# PIO.net
KiCad netlist of a schematic drawn in Altium Designer
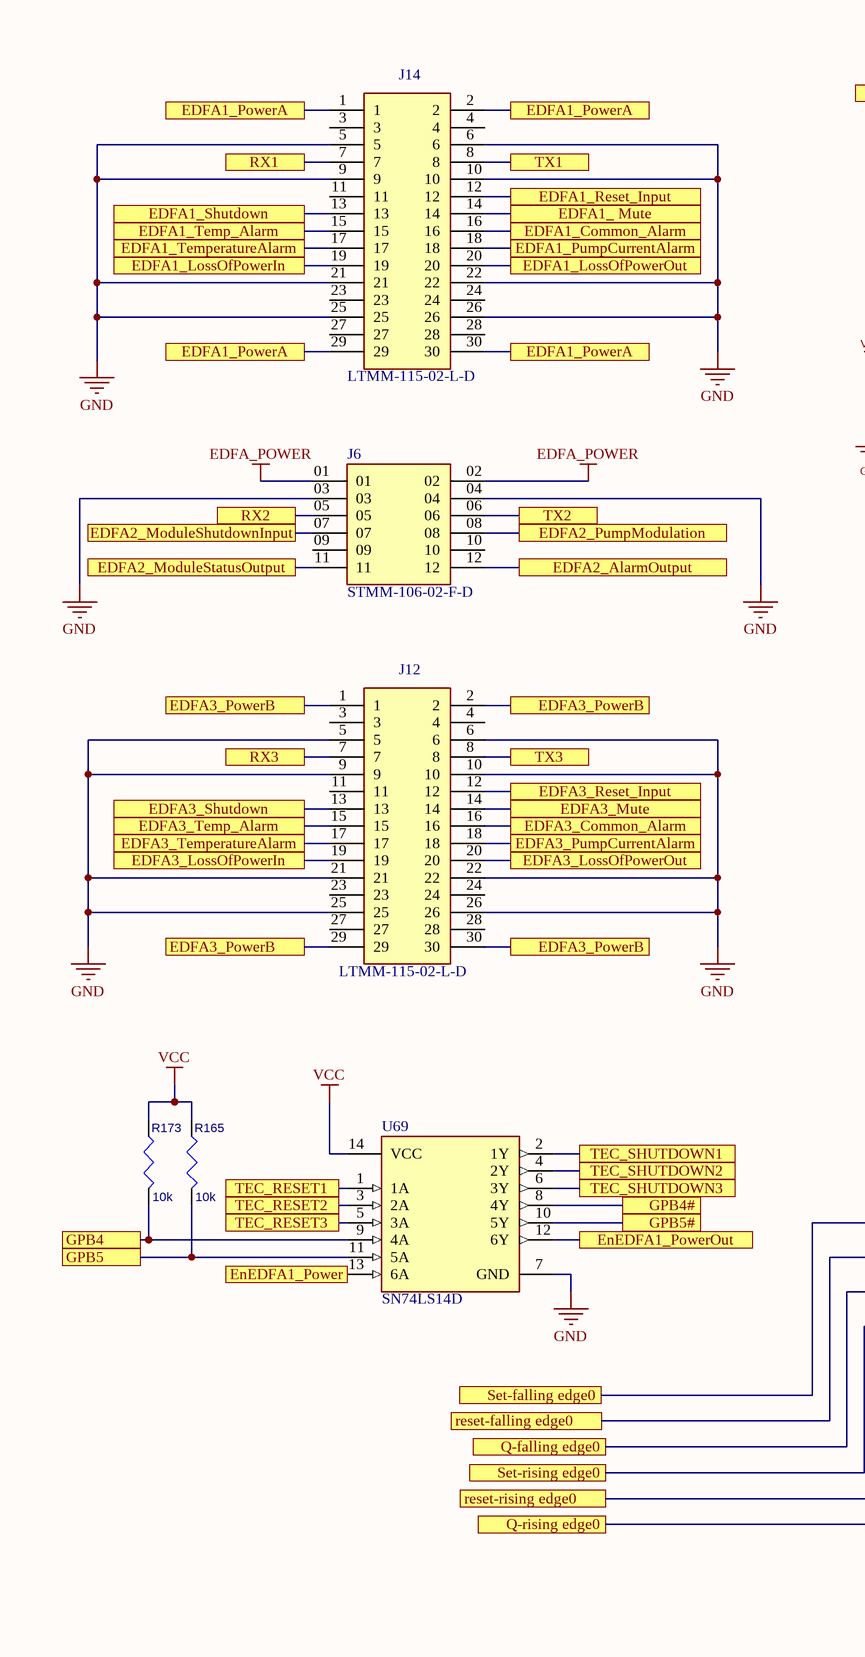
[diagram p0: PIO.SchDoc, left]
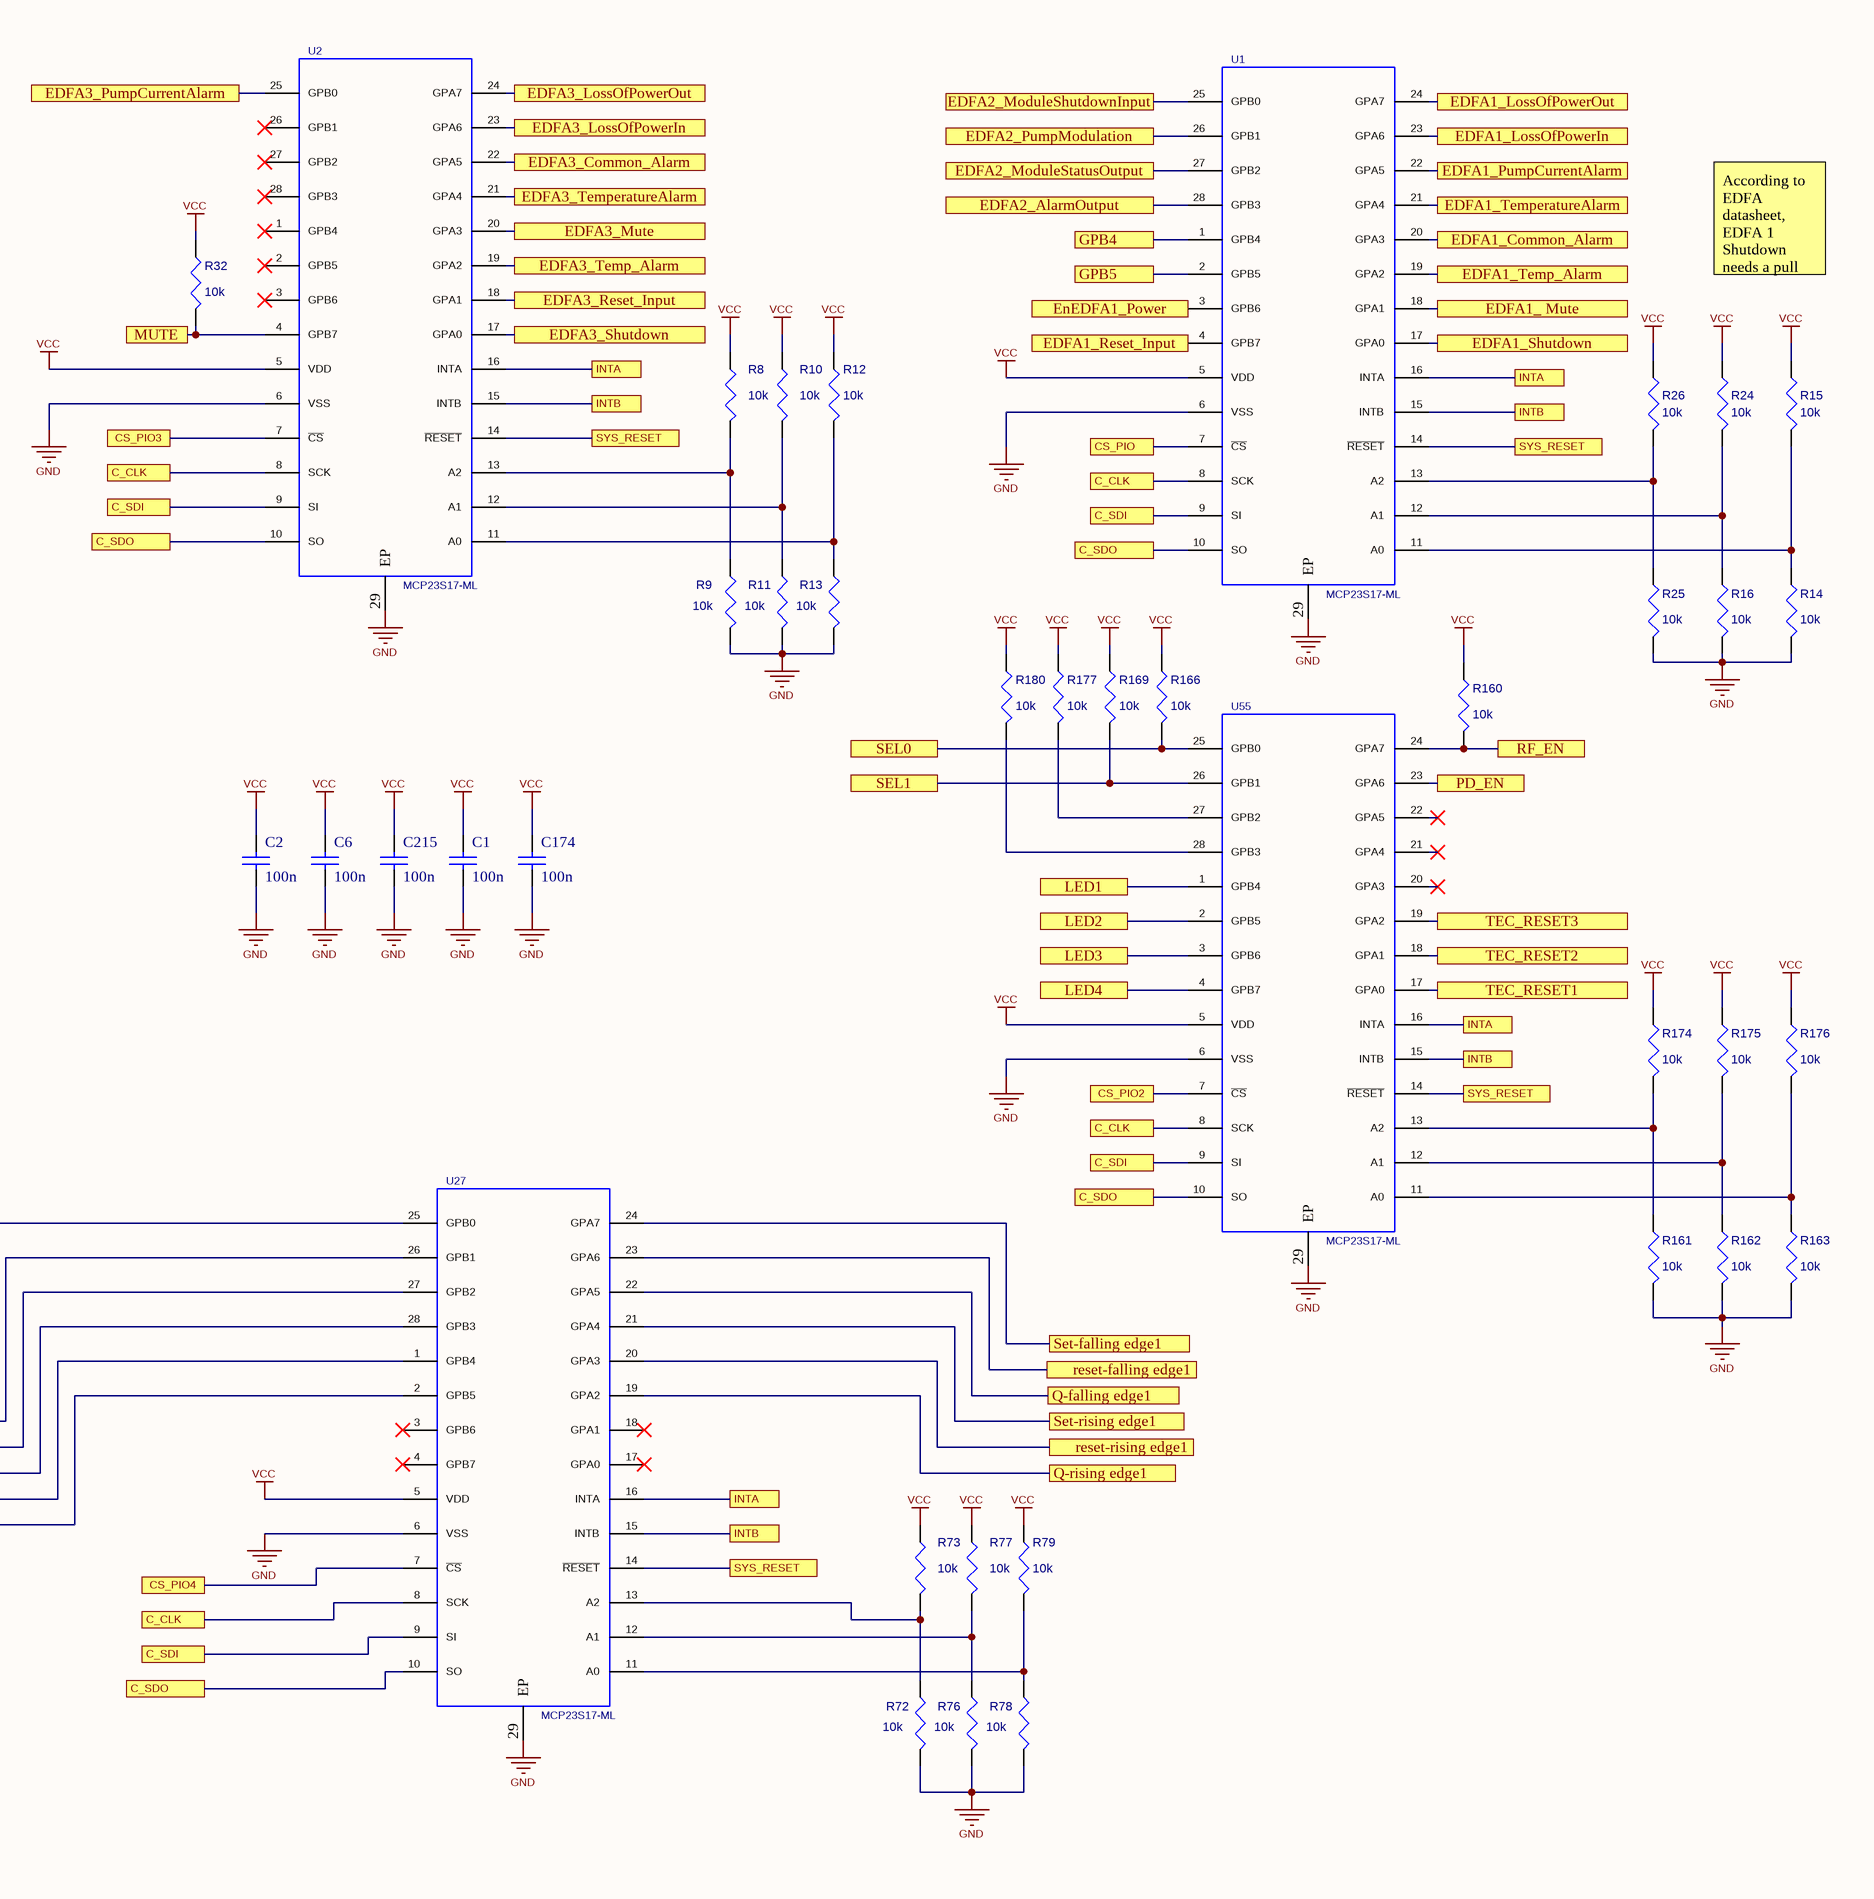
[diagram p1: PIO.SchDoc, right]

(export (version "E")
  (design (tool "Eeschema 10.0.6"))
  (components
    (comp (ref "C1")
      (value "100n")
      (footprint "CAPC1608X90X35LL15T15")
      (description "Chip Capacitor, 100 nF, +/- 10%, 50 V, -55 to 125 degC, 0603 (1608 Metric), RoHS, Tape and Reel")
      (fields (field (name "TOLERANCE") "10%") (field (name "MANUFACTURER") "KEMET"))
      (libsource (lib "xDAC_Carrier") (part "CMP-1035-02592-3"))
    )
    (comp (ref "C2")
      (value "100n")
      (footprint "CAPC1608X90X35LL15T15")
      (description "Chip Capacitor, 100 nF, +/- 10%, 50 V, -55 to 125 degC, 0603 (1608 Metric), RoHS, Tape and Reel")
      (fields (field (name "TOLERANCE") "10%") (field (name "MANUFACTURER") "KEMET"))
      (libsource (lib "xDAC_Carrier") (part "CMP-1035-02592-3"))
    )
    (comp (ref "C6")
      (value "100n")
      (footprint "CAPC1608X90X35LL15T15")
      (description "Chip Capacitor, 100 nF, +/- 10%, 50 V, -55 to 125 degC, 0603 (1608 Metric), RoHS, Tape and Reel")
      (fields (field (name "TOLERANCE") "10%") (field (name "MANUFACTURER") "KEMET"))
      (libsource (lib "xDAC_Carrier") (part "CMP-1035-02592-3"))
    )
    (comp (ref "C174")
      (value "100n")
      (footprint "CAPC1608X90X35LL15T15")
      (description "Chip Capacitor, 100 nF, +/- 10%, 50 V, -55 to 125 degC, 0603 (1608 Metric), RoHS, Tape and Reel")
      (fields (field (name "TOLERANCE") "10%") (field (name "MANUFACTURER") "KEMET"))
      (libsource (lib "xDAC_Carrier") (part "CMP-1035-02592-3"))
    )
    (comp (ref "C215")
      (value "100n")
      (footprint "CAPC1608X90X35LL15T15")
      (description "Chip Capacitor, 100 nF, +/- 10%, 50 V, -55 to 125 degC, 0603 (1608 Metric), RoHS, Tape and Reel")
      (fields (field (name "TOLERANCE") "10%") (field (name "MANUFACTURER") "KEMET"))
      (libsource (lib "xDAC_Carrier") (part "CMP-1035-02592-3"))
    )
    (comp (ref "J6")
      (value "STMM-106-02-F-D")
      (footprint "SAMTEC_STMM-106-02-F-D")
      (description "Connector Header Surface Mount 12 position 0.079 (2.00mm)")
      (fields (field (name "MF") "Samtec"))
      (libsource (lib "xDAC_Carrier") (part "STMM-106-02-F-D"))
    )
    (comp (ref "J12")
      (value "LTMM-115-02-L-D")
      (footprint "SHDR30W51P200_2X15_3239X651X480P")
      (description "Connector")
      (fields (field (name "MOUSER PART NUMBER") "200-LTMM11502LD"))
      (libsource (lib "xDAC_Carrier") (part "LTMM-115-02-L-D"))
    )
    (comp (ref "J14")
      (value "LTMM-115-02-L-D")
      (footprint "SHDR30W51P200_2X15_3239X651X480P")
      (description "Connector")
      (fields (field (name "MOUSER PART NUMBER") "200-LTMM11502LD"))
      (libsource (lib "xDAC_Carrier") (part "LTMM-115-02-L-D"))
    )
    (comp (ref "R8")
      (value "10k")
      (footprint "CR0603N")
      (description "RES.,10k OHMS,1%,1/10W,0603")
      (fields (field (name "MANUFACTURER") "PANASONIC") (field (name "TOLERANCE") "1%"))
      (libsource (lib "xDAC_Carrier") (part "RES"))
    )
    (comp (ref "R9")
      (value "10k")
      (footprint "CR0603N")
      (description "RES.,10k OHMS,1%,1/10W,0603")
      (fields (field (name "MANUFACTURER") "PANASONIC") (field (name "TOLERANCE") "1%"))
      (libsource (lib "xDAC_Carrier") (part "RES"))
    )
    (comp (ref "R10")
      (value "10k")
      (footprint "CR0603N")
      (description "RES.,10k OHMS,1%,1/10W,0603")
      (fields (field (name "MANUFACTURER") "PANASONIC") (field (name "TOLERANCE") "1%"))
      (libsource (lib "xDAC_Carrier") (part "RES"))
    )
    (comp (ref "R11")
      (value "10k")
      (footprint "CR0603N")
      (description "RES.,10k OHMS,1%,1/10W,0603")
      (fields (field (name "MANUFACTURER") "PANASONIC") (field (name "TOLERANCE") "1%"))
      (libsource (lib "xDAC_Carrier") (part "RES"))
    )
    (comp (ref "R12")
      (value "10k")
      (footprint "CR0603N")
      (description "RES.,10k OHMS,1%,1/10W,0603")
      (fields (field (name "MANUFACTURER") "PANASONIC") (field (name "TOLERANCE") "1%"))
      (libsource (lib "xDAC_Carrier") (part "RES"))
    )
    (comp (ref "R13")
      (value "10k")
      (footprint "CR0603N")
      (description "RES.,10k OHMS,1%,1/10W,0603")
      (fields (field (name "MANUFACTURER") "PANASONIC") (field (name "TOLERANCE") "1%"))
      (libsource (lib "xDAC_Carrier") (part "RES"))
    )
    (comp (ref "R14")
      (value "10k")
      (footprint "CR0603N")
      (description "RES.,10k OHMS,1%,1/10W,0603")
      (fields (field (name "MANUFACTURER") "PANASONIC") (field (name "TOLERANCE") "1%"))
      (libsource (lib "xDAC_Carrier") (part "RES"))
    )
    (comp (ref "R15")
      (value "10k")
      (footprint "CR0603N")
      (description "RES.,10k OHMS,1%,1/10W,0603")
      (fields (field (name "MANUFACTURER") "PANASONIC") (field (name "TOLERANCE") "1%"))
      (libsource (lib "xDAC_Carrier") (part "RES"))
    )
    (comp (ref "R16")
      (value "10k")
      (footprint "CR0603N")
      (description "RES.,10k OHMS,1%,1/10W,0603")
      (fields (field (name "MANUFACTURER") "PANASONIC") (field (name "TOLERANCE") "1%"))
      (libsource (lib "xDAC_Carrier") (part "RES"))
    )
    (comp (ref "R24")
      (value "10k")
      (footprint "CR0603N")
      (description "RES.,10k OHMS,1%,1/10W,0603")
      (fields (field (name "MANUFACTURER") "PANASONIC") (field (name "TOLERANCE") "1%"))
      (libsource (lib "xDAC_Carrier") (part "RES"))
    )
    (comp (ref "R25")
      (value "10k")
      (footprint "CR0603N")
      (description "RES.,10k OHMS,1%,1/10W,0603")
      (fields (field (name "MANUFACTURER") "PANASONIC") (field (name "TOLERANCE") "1%"))
      (libsource (lib "xDAC_Carrier") (part "RES"))
    )
    (comp (ref "R26")
      (value "10k")
      (footprint "CR0603N")
      (description "RES.,10k OHMS,1%,1/10W,0603")
      (fields (field (name "MANUFACTURER") "PANASONIC") (field (name "TOLERANCE") "1%"))
      (libsource (lib "xDAC_Carrier") (part "RES"))
    )
    (comp (ref "R32")
      (value "10k")
      (footprint "CR0603N")
      (description "RES.,10k OHMS,1%,1/10W,0603")
      (fields (field (name "MANUFACTURER") "PANASONIC") (field (name "TOLERANCE") "1%"))
      (libsource (lib "xDAC_Carrier") (part "RES"))
    )
    (comp (ref "R72")
      (value "10k")
      (footprint "CR0603N")
      (description "RES.,10k OHMS,1%,1/10W,0603")
      (fields (field (name "MANUFACTURER") "PANASONIC") (field (name "TOLERANCE") "1%"))
      (libsource (lib "xDAC_Carrier") (part "RES"))
    )
    (comp (ref "R73")
      (value "10k")
      (footprint "CR0603N")
      (description "RES.,10k OHMS,1%,1/10W,0603")
      (fields (field (name "MANUFACTURER") "PANASONIC") (field (name "TOLERANCE") "1%"))
      (libsource (lib "xDAC_Carrier") (part "RES"))
    )
    (comp (ref "R76")
      (value "10k")
      (footprint "CR0603N")
      (description "RES.,10k OHMS,1%,1/10W,0603")
      (fields (field (name "MANUFACTURER") "PANASONIC") (field (name "TOLERANCE") "1%"))
      (libsource (lib "xDAC_Carrier") (part "RES"))
    )
    (comp (ref "R77")
      (value "10k")
      (footprint "CR0603N")
      (description "RES.,10k OHMS,1%,1/10W,0603")
      (fields (field (name "MANUFACTURER") "PANASONIC") (field (name "TOLERANCE") "1%"))
      (libsource (lib "xDAC_Carrier") (part "RES"))
    )
    (comp (ref "R78")
      (value "10k")
      (footprint "CR0603N")
      (description "RES.,10k OHMS,1%,1/10W,0603")
      (fields (field (name "MANUFACTURER") "PANASONIC") (field (name "TOLERANCE") "1%"))
      (libsource (lib "xDAC_Carrier") (part "RES"))
    )
    (comp (ref "R79")
      (value "10k")
      (footprint "CR0603N")
      (description "RES.,10k OHMS,1%,1/10W,0603")
      (fields (field (name "MANUFACTURER") "PANASONIC") (field (name "TOLERANCE") "1%"))
      (libsource (lib "xDAC_Carrier") (part "RES"))
    )
    (comp (ref "R160")
      (value "10k")
      (footprint "CR0603N")
      (description "RES.,10k OHMS,1%,1/10W,0603")
      (fields (field (name "MANUFACTURER") "PANASONIC") (field (name "TOLERANCE") "1%"))
      (libsource (lib "xDAC_Carrier") (part "RES"))
    )
    (comp (ref "R161")
      (value "10k")
      (footprint "CR0603N")
      (description "RES.,10k OHMS,1%,1/10W,0603")
      (fields (field (name "MANUFACTURER") "PANASONIC") (field (name "TOLERANCE") "1%"))
      (libsource (lib "xDAC_Carrier") (part "RES"))
    )
    (comp (ref "R162")
      (value "10k")
      (footprint "CR0603N")
      (description "RES.,10k OHMS,1%,1/10W,0603")
      (fields (field (name "MANUFACTURER") "PANASONIC") (field (name "TOLERANCE") "1%"))
      (libsource (lib "xDAC_Carrier") (part "RES"))
    )
    (comp (ref "R163")
      (value "10k")
      (footprint "CR0603N")
      (description "RES.,10k OHMS,1%,1/10W,0603")
      (fields (field (name "MANUFACTURER") "PANASONIC") (field (name "TOLERANCE") "1%"))
      (libsource (lib "xDAC_Carrier") (part "RES"))
    )
    (comp (ref "R165")
      (value "10k")
      (footprint "CR0603N")
      (description "RES.,10k OHMS,1%,1/10W,0603")
      (fields (field (name "MANUFACTURER") "PANASONIC") (field (name "TOLERANCE") "1%"))
      (libsource (lib "xDAC_Carrier") (part "RES"))
    )
    (comp (ref "R166")
      (value "10k")
      (footprint "CR0603N")
      (description "RES.,10k OHMS,1%,1/10W,0603")
      (fields (field (name "MANUFACTURER") "PANASONIC") (field (name "TOLERANCE") "1%"))
      (libsource (lib "xDAC_Carrier") (part "RES"))
    )
    (comp (ref "R169")
      (value "10k")
      (footprint "CR0603N")
      (description "RES.,10k OHMS,1%,1/10W,0603")
      (fields (field (name "MANUFACTURER") "PANASONIC") (field (name "TOLERANCE") "1%"))
      (libsource (lib "xDAC_Carrier") (part "RES"))
    )
    (comp (ref "R173")
      (value "10k")
      (footprint "CR0603N")
      (description "RES.,10k OHMS,1%,1/10W,0603")
      (fields (field (name "MANUFACTURER") "PANASONIC") (field (name "TOLERANCE") "1%"))
      (libsource (lib "xDAC_Carrier") (part "RES"))
    )
    (comp (ref "R174")
      (value "10k")
      (footprint "CR0603N")
      (description "RES.,10k OHMS,1%,1/10W,0603")
      (fields (field (name "MANUFACTURER") "PANASONIC") (field (name "TOLERANCE") "1%"))
      (libsource (lib "xDAC_Carrier") (part "RES"))
    )
    (comp (ref "R175")
      (value "10k")
      (footprint "CR0603N")
      (description "RES.,10k OHMS,1%,1/10W,0603")
      (fields (field (name "MANUFACTURER") "PANASONIC") (field (name "TOLERANCE") "1%"))
      (libsource (lib "xDAC_Carrier") (part "RES"))
    )
    (comp (ref "R176")
      (value "10k")
      (footprint "CR0603N")
      (description "RES.,10k OHMS,1%,1/10W,0603")
      (fields (field (name "MANUFACTURER") "PANASONIC") (field (name "TOLERANCE") "1%"))
      (libsource (lib "xDAC_Carrier") (part "RES"))
    )
    (comp (ref "R177")
      (value "10k")
      (footprint "CR0603N")
      (description "RES.,10k OHMS,1%,1/10W,0603")
      (fields (field (name "MANUFACTURER") "PANASONIC") (field (name "TOLERANCE") "1%"))
      (libsource (lib "xDAC_Carrier") (part "RES"))
    )
    (comp (ref "R180")
      (value "10k")
      (footprint "CR0603N")
      (description "RES.,10k OHMS,1%,1/10W,0603")
      (fields (field (name "MANUFACTURER") "PANASONIC") (field (name "TOLERANCE") "1%"))
      (libsource (lib "xDAC_Carrier") (part "RES"))
    )
    (comp (ref "U1")
      (value "MCP23S17-ML")
      (footprint "QFN65P600X600X100-29VN")
      (fields (field (name "MANUFACTURER") "Microchip") (field (name "PART NO") "MCP23S17-E/ML"))
      (libsource (lib "xDAC_Carrier") (part "MCP23S17-ML"))
    )
    (comp (ref "U2")
      (value "MCP23S17-ML")
      (footprint "QFN65P600X600X100-29VN")
      (fields (field (name "MANUFACTURER") "Microchip") (field (name "PART NO") "MCP23S17-E/ML"))
      (libsource (lib "xDAC_Carrier") (part "MCP23S17-ML"))
    )
    (comp (ref "U27")
      (value "MCP23S17-ML")
      (footprint "QFN65P600X600X100-29VN")
      (fields (field (name "MANUFACTURER") "Microchip") (field (name "PART NO") "MCP23S17-E/ML"))
      (libsource (lib "xDAC_Carrier") (part "MCP23S17-ML"))
    )
    (comp (ref "U55")
      (value "MCP23S17-ML")
      (footprint "QFN65P600X600X100-29VN")
      (fields (field (name "MANUFACTURER") "Microchip") (field (name "PART NO") "MCP23S17-E/ML"))
      (libsource (lib "xDAC_Carrier") (part "MCP23S17-ML"))
    )
    (comp (ref "U69")
      (value "SN74LS14D")
      (footprint "FP-D0014A-MFG")
      (description "IC INVERTER SCHMITT 6CH 14SOIC")
      (fields
        (field (name "OCTOPART") "https://octopart.com/sn74ls14d-texas+instruments-464458")
        (field (name "MANUFACTURER") "Texas Instruments")
      )
      (libsource (lib "Altium Content Vault") (part "988d500a1b54a36af656cee24e4e601"))
    )
  )
  (nets
    (net (code "1") (name "/CS_PIO") (class "Default")
      (node (ref "U1") (pin "7") (pinfunction "CS_7") (pintype "passive"))
    )
    (net (code "2") (name "/CS_PIO2") (class "Default")
      (node (ref "U55") (pin "7") (pinfunction "CS_7") (pintype "passive"))
    )
    (net (code "3") (name "/CS_PIO3") (class "Default")
      (node (ref "U2") (pin "7") (pinfunction "CS_7") (pintype "passive"))
    )
    (net (code "4") (name "/CS_PIO4") (class "Default")
      (node (ref "U27") (pin "7") (pinfunction "CS_7") (pintype "passive"))
    )
    (net (code "5") (name "/C_CLK") (class "Default")
      (node (ref "U1") (pin "8") (pinfunction "SCK_8") (pintype "passive"))
      (node (ref "U2") (pin "8") (pinfunction "SCK_8") (pintype "passive"))
      (node (ref "U27") (pin "8") (pinfunction "SCK_8") (pintype "passive"))
      (node (ref "U55") (pin "8") (pinfunction "SCK_8") (pintype "passive"))
    )
    (net (code "6") (name "/C_SDI") (class "Default")
      (node (ref "U1") (pin "9") (pinfunction "SI_9") (pintype "passive"))
      (node (ref "U2") (pin "9") (pinfunction "SI_9") (pintype "passive"))
      (node (ref "U27") (pin "9") (pinfunction "SI_9") (pintype "passive"))
      (node (ref "U55") (pin "9") (pinfunction "SI_9") (pintype "passive"))
    )
    (net (code "7") (name "/C_SDO") (class "Default")
      (node (ref "U1") (pin "10") (pinfunction "SO_10") (pintype "passive"))
      (node (ref "U2") (pin "10") (pinfunction "SO_10") (pintype "passive"))
      (node (ref "U27") (pin "10") (pinfunction "SO_10") (pintype "passive"))
      (node (ref "U55") (pin "10") (pinfunction "SO_10") (pintype "passive"))
    )
    (net (code "8") (name "/EDFA1_ Mute") (class "Default")
      (node (ref "J14") (pin "14") (pinfunction "14_14") (pintype "passive"))
      (node (ref "U1") (pin "18") (pinfunction "GPA1_18") (pintype "passive"))
    )
    (net (code "9") (name "/EDFA1_Common_Alarm") (class "Default")
      (node (ref "J14") (pin "16") (pinfunction "16_16") (pintype "passive"))
      (node (ref "U1") (pin "20") (pinfunction "GPA3_20") (pintype "passive"))
    )
    (net (code "10") (name "/EDFA1_LossOfPowerIn") (class "Default")
      (node (ref "J14") (pin "19") (pinfunction "19_19") (pintype "passive"))
      (node (ref "U1") (pin "23") (pinfunction "GPA6_23") (pintype "passive"))
    )
    (net (code "11") (name "/EDFA1_LossOfPowerOut") (class "Default")
      (node (ref "J14") (pin "20") (pinfunction "20_20") (pintype "passive"))
      (node (ref "U1") (pin "24") (pinfunction "GPA7_24") (pintype "passive"))
    )
    (net (code "12") (name "/EDFA1_PowerA") (class "Default")
      (node (ref "J14") (pin "1") (pinfunction "1_1") (pintype "passive"))
      (node (ref "J14") (pin "2") (pinfunction "2_2") (pintype "passive"))
      (node (ref "J14") (pin "29") (pinfunction "29_29") (pintype "passive"))
      (node (ref "J14") (pin "30") (pinfunction "30_30") (pintype "passive"))
    )
    (net (code "13") (name "/EDFA1_PumpCurrentAlarm") (class "Default")
      (node (ref "J14") (pin "18") (pinfunction "18_18") (pintype "passive"))
      (node (ref "U1") (pin "22") (pinfunction "GPA5_22") (pintype "passive"))
    )
    (net (code "14") (name "/EDFA1_Reset_Input") (class "Default")
      (node (ref "J14") (pin "12") (pinfunction "12_12") (pintype "passive"))
      (node (ref "U1") (pin "4") (pinfunction "GPB7_4") (pintype "passive"))
    )
    (net (code "15") (name "/EDFA1_Shutdown") (class "Default")
      (node (ref "J14") (pin "13") (pinfunction "13_13") (pintype "passive"))
      (node (ref "U1") (pin "17") (pinfunction "GPA0_17") (pintype "passive"))
    )
    (net (code "16") (name "/EDFA1_Temp_Alarm") (class "Default")
      (node (ref "J14") (pin "15") (pinfunction "15_15") (pintype "passive"))
      (node (ref "U1") (pin "19") (pinfunction "GPA2_19") (pintype "passive"))
    )
    (net (code "17") (name "/EDFA1_TemperatureAlarm") (class "Default")
      (node (ref "J14") (pin "17") (pinfunction "17_17") (pintype "passive"))
      (node (ref "U1") (pin "21") (pinfunction "GPA4_21") (pintype "passive"))
    )
    (net (code "18") (name "/EDFA2_AlarmOutput") (class "Default")
      (node (ref "J6") (pin "12") (pinfunction "12_12") (pintype "passive"))
      (node (ref "U1") (pin "28") (pinfunction "GPB3_28") (pintype "passive"))
    )
    (net (code "19") (name "/EDFA2_ModuleShutdownInput") (class "Default")
      (node (ref "J6") (pin "07") (pinfunction "07_07") (pintype "passive"))
      (node (ref "U1") (pin "25") (pinfunction "GPB0_25") (pintype "passive"))
    )
    (net (code "20") (name "/EDFA2_ModuleStatusOutput") (class "Default")
      (node (ref "J6") (pin "11") (pinfunction "11_11") (pintype "passive"))
      (node (ref "U1") (pin "27") (pinfunction "GPB2_27") (pintype "passive"))
    )
    (net (code "21") (name "/EDFA2_PumpModulation") (class "Default")
      (node (ref "J6") (pin "08") (pinfunction "08_08") (pintype "passive"))
      (node (ref "U1") (pin "26") (pinfunction "GPB1_26") (pintype "passive"))
    )
    (net (code "22") (name "/EDFA3_Common_Alarm") (class "Default")
      (node (ref "J12") (pin "16") (pinfunction "16_16") (pintype "passive"))
      (node (ref "U2") (pin "22") (pinfunction "GPA5_22") (pintype "passive"))
    )
    (net (code "23") (name "/EDFA3_LossOfPowerIn") (class "Default")
      (node (ref "J12") (pin "19") (pinfunction "19_19") (pintype "passive"))
      (node (ref "U2") (pin "23") (pinfunction "GPA6_23") (pintype "passive"))
    )
    (net (code "24") (name "/EDFA3_LossOfPowerOut") (class "Default")
      (node (ref "J12") (pin "20") (pinfunction "20_20") (pintype "passive"))
      (node (ref "U2") (pin "24") (pinfunction "GPA7_24") (pintype "passive"))
    )
    (net (code "25") (name "/EDFA3_Mute") (class "Default")
      (node (ref "J12") (pin "14") (pinfunction "14_14") (pintype "passive"))
      (node (ref "U2") (pin "20") (pinfunction "GPA3_20") (pintype "passive"))
    )
    (net (code "26") (name "/EDFA3_PowerB") (class "Default")
      (node (ref "J12") (pin "1") (pinfunction "1_1") (pintype "passive"))
      (node (ref "J12") (pin "2") (pinfunction "2_2") (pintype "passive"))
      (node (ref "J12") (pin "29") (pinfunction "29_29") (pintype "passive"))
      (node (ref "J12") (pin "30") (pinfunction "30_30") (pintype "passive"))
    )
    (net (code "27") (name "/EDFA3_PumpCurrentAlarm") (class "Default")
      (node (ref "J12") (pin "18") (pinfunction "18_18") (pintype "passive"))
      (node (ref "U2") (pin "25") (pinfunction "GPB0_25") (pintype "passive"))
    )
    (net (code "28") (name "/EDFA3_Reset_Input") (class "Default")
      (node (ref "J12") (pin "12") (pinfunction "12_12") (pintype "passive"))
      (node (ref "U2") (pin "18") (pinfunction "GPA1_18") (pintype "passive"))
    )
    (net (code "29") (name "/EDFA3_Shutdown") (class "Default")
      (node (ref "J12") (pin "13") (pinfunction "13_13") (pintype "passive"))
      (node (ref "U2") (pin "17") (pinfunction "GPA0_17") (pintype "passive"))
    )
    (net (code "30") (name "/EDFA3_Temp_Alarm") (class "Default")
      (node (ref "J12") (pin "15") (pinfunction "15_15") (pintype "passive"))
      (node (ref "U2") (pin "19") (pinfunction "GPA2_19") (pintype "passive"))
    )
    (net (code "31") (name "/EDFA3_TemperatureAlarm") (class "Default")
      (node (ref "J12") (pin "17") (pinfunction "17_17") (pintype "passive"))
      (node (ref "U2") (pin "21") (pinfunction "GPA4_21") (pintype "passive"))
    )
    (net (code "32") (name "/EnEDFA1_Power") (class "Default")
      (node (ref "U1") (pin "3") (pinfunction "GPB6_3") (pintype "passive"))
      (node (ref "U69") (pin "13") (pinfunction "6A_13") (pintype "input"))
    )
    (net (code "33") (name "/EnEDFA1_PowerOut") (class "Default")
      (node (ref "U69") (pin "12") (pinfunction "6Y_12") (pintype "output"))
    )
    (net (code "34") (name "/GPB4") (class "Default")
      (node (ref "R173") (pin "2") (pinfunction "2_2") (pintype "passive"))
      (node (ref "U1") (pin "1") (pinfunction "GPB4_1") (pintype "passive"))
      (node (ref "U69") (pin "9") (pinfunction "4A_9") (pintype "input"))
    )
    (net (code "35") (name "/GPB4#") (class "Default")
      (node (ref "U69") (pin "8") (pinfunction "4Y_8") (pintype "output"))
    )
    (net (code "36") (name "/GPB5") (class "Default")
      (node (ref "R165") (pin "2") (pinfunction "2_2") (pintype "passive"))
      (node (ref "U1") (pin "2") (pinfunction "GPB5_2") (pintype "passive"))
      (node (ref "U69") (pin "11") (pinfunction "5A_11") (pintype "input"))
    )
    (net (code "37") (name "/GPB5#") (class "Default")
      (node (ref "U69") (pin "10") (pinfunction "5Y_10") (pintype "output"))
    )
    (net (code "38") (name "/INTA") (class "Default")
      (node (ref "U1") (pin "16") (pinfunction "INTA_16") (pintype "passive"))
      (node (ref "U2") (pin "16") (pinfunction "INTA_16") (pintype "passive"))
      (node (ref "U27") (pin "16") (pinfunction "INTA_16") (pintype "passive"))
      (node (ref "U55") (pin "16") (pinfunction "INTA_16") (pintype "passive"))
    )
    (net (code "39") (name "/INTB") (class "Default")
      (node (ref "U1") (pin "15") (pinfunction "INTB_15") (pintype "passive"))
      (node (ref "U2") (pin "15") (pinfunction "INTB_15") (pintype "passive"))
      (node (ref "U27") (pin "15") (pinfunction "INTB_15") (pintype "passive"))
      (node (ref "U55") (pin "15") (pinfunction "INTB_15") (pintype "passive"))
    )
    (net (code "40") (name "/LED1") (class "Default")
      (node (ref "U55") (pin "1") (pinfunction "GPB4_1") (pintype "passive"))
    )
    (net (code "41") (name "/LED2") (class "Default")
      (node (ref "U55") (pin "2") (pinfunction "GPB5_2") (pintype "passive"))
    )
    (net (code "42") (name "/LED3") (class "Default")
      (node (ref "U55") (pin "3") (pinfunction "GPB6_3") (pintype "passive"))
    )
    (net (code "43") (name "/LED4") (class "Default")
      (node (ref "U55") (pin "4") (pinfunction "GPB7_4") (pintype "passive"))
    )
    (net (code "44") (name "/MUTE") (class "Default")
      (node (ref "R32") (pin "2") (pinfunction "2_2") (pintype "passive"))
      (node (ref "U2") (pin "4") (pinfunction "GPB7_4") (pintype "passive"))
    )
    (net (code "45") (name "/PD_EN") (class "Default")
      (node (ref "U55") (pin "23") (pinfunction "GPA6_23") (pintype "passive"))
    )
    (net (code "46") (name "/Q-falling edge0") (class "Default")
      (node (ref "U27") (pin "27") (pinfunction "GPB2_27") (pintype "passive"))
    )
    (net (code "47") (name "/Q-falling edge1") (class "Default")
      (node (ref "U27") (pin "22") (pinfunction "GPA5_22") (pintype "passive"))
    )
    (net (code "48") (name "/Q-rising edge0") (class "Default")
      (node (ref "U27") (pin "2") (pinfunction "GPB5_2") (pintype "passive"))
    )
    (net (code "49") (name "/Q-rising edge1") (class "Default")
      (node (ref "U27") (pin "19") (pinfunction "GPA2_19") (pintype "passive"))
    )
    (net (code "50") (name "/RF_EN") (class "Default")
      (node (ref "R160") (pin "2") (pinfunction "2_2") (pintype "passive"))
      (node (ref "U55") (pin "24") (pinfunction "GPA7_24") (pintype "passive"))
    )
    (net (code "51") (name "/RX1") (class "Default")
      (node (ref "J14") (pin "7") (pinfunction "7_7") (pintype "passive"))
    )
    (net (code "52") (name "/RX2") (class "Default")
      (node (ref "J6") (pin "05") (pinfunction "05_05") (pintype "passive"))
    )
    (net (code "53") (name "/RX3") (class "Default")
      (node (ref "J12") (pin "7") (pinfunction "7_7") (pintype "passive"))
    )
    (net (code "54") (name "/SEL0") (class "Default")
      (node (ref "R166") (pin "2") (pinfunction "2_2") (pintype "passive"))
      (node (ref "U55") (pin "25") (pinfunction "GPB0_25") (pintype "passive"))
    )
    (net (code "55") (name "/SEL1") (class "Default")
      (node (ref "R169") (pin "2") (pinfunction "2_2") (pintype "passive"))
      (node (ref "U55") (pin "26") (pinfunction "GPB1_26") (pintype "passive"))
    )
    (net (code "56") (name "/SYS_RESET") (class "Default")
      (node (ref "U1") (pin "14") (pinfunction "RESET_14") (pintype "passive"))
      (node (ref "U2") (pin "14") (pinfunction "RESET_14") (pintype "passive"))
      (node (ref "U27") (pin "14") (pinfunction "RESET_14") (pintype "passive"))
      (node (ref "U55") (pin "14") (pinfunction "RESET_14") (pintype "passive"))
    )
    (net (code "57") (name "/Set-falling edge0") (class "Default")
      (node (ref "U27") (pin "25") (pinfunction "GPB0_25") (pintype "passive"))
    )
    (net (code "58") (name "/Set-falling edge1") (class "Default")
      (node (ref "U27") (pin "24") (pinfunction "GPA7_24") (pintype "passive"))
    )
    (net (code "59") (name "/Set-rising edge0") (class "Default")
      (node (ref "U27") (pin "28") (pinfunction "GPB3_28") (pintype "passive"))
    )
    (net (code "60") (name "/Set-rising edge1") (class "Default")
      (node (ref "U27") (pin "21") (pinfunction "GPA4_21") (pintype "passive"))
    )
    (net (code "61") (name "/TEC_RESET1") (class "Default")
      (node (ref "U55") (pin "17") (pinfunction "GPA0_17") (pintype "passive"))
      (node (ref "U69") (pin "1") (pinfunction "1A_1") (pintype "input"))
    )
    (net (code "62") (name "/TEC_RESET2") (class "Default")
      (node (ref "U55") (pin "18") (pinfunction "GPA1_18") (pintype "passive"))
      (node (ref "U69") (pin "3") (pinfunction "2A_3") (pintype "input"))
    )
    (net (code "63") (name "/TEC_RESET3") (class "Default")
      (node (ref "U55") (pin "19") (pinfunction "GPA2_19") (pintype "passive"))
      (node (ref "U69") (pin "5") (pinfunction "3A_5") (pintype "input"))
    )
    (net (code "64") (name "/TEC_SHUTDOWN1") (class "Default")
      (node (ref "U69") (pin "2") (pinfunction "1Y_2") (pintype "output"))
    )
    (net (code "65") (name "/TEC_SHUTDOWN2") (class "Default")
      (node (ref "U69") (pin "4") (pinfunction "2Y_4") (pintype "output"))
    )
    (net (code "66") (name "/TEC_SHUTDOWN3") (class "Default")
      (node (ref "U69") (pin "6") (pinfunction "3Y_6") (pintype "output"))
    )
    (net (code "67") (name "/TX1") (class "Default")
      (node (ref "J14") (pin "8") (pinfunction "8_8") (pintype "passive"))
    )
    (net (code "68") (name "/TX2") (class "Default")
      (node (ref "J6") (pin "06") (pinfunction "06_06") (pintype "passive"))
    )
    (net (code "69") (name "/TX3") (class "Default")
      (node (ref "J12") (pin "8") (pinfunction "8_8") (pintype "passive"))
    )
    (net (code "70") (name "/reset-falling edge0") (class "Default")
      (node (ref "U27") (pin "26") (pinfunction "GPB1_26") (pintype "passive"))
    )
    (net (code "71") (name "/reset-falling edge1") (class "Default")
      (node (ref "U27") (pin "23") (pinfunction "GPA6_23") (pintype "passive"))
    )
    (net (code "72") (name "/reset-rising edge0") (class "Default")
      (node (ref "U27") (pin "1") (pinfunction "GPB4_1") (pintype "passive"))
    )
    (net (code "73") (name "/reset-rising edge1") (class "Default")
      (node (ref "U27") (pin "20") (pinfunction "GPA3_20") (pintype "passive"))
    )
    (net (code "74") (name "EDFA_POWER") (class "Default")
      (node (ref "J6") (pin "01") (pinfunction "01_01") (pintype "passive"))
      (node (ref "J6") (pin "02") (pinfunction "02_02") (pintype "passive"))
    )
    (net (code "75") (name "GND") (class "Default")
      (node (ref "C1") (pin "2") (pinfunction "2_2") (pintype "passive"))
      (node (ref "C174") (pin "2") (pinfunction "2_2") (pintype "passive"))
      (node (ref "C2") (pin "2") (pinfunction "2_2") (pintype "passive"))
      (node (ref "C215") (pin "2") (pinfunction "2_2") (pintype "passive"))
      (node (ref "C6") (pin "2") (pinfunction "2_2") (pintype "passive"))
      (node (ref "J12") (pin "10") (pinfunction "10_10") (pintype "passive"))
      (node (ref "J12") (pin "21") (pinfunction "21_21") (pintype "passive"))
      (node (ref "J12") (pin "22") (pinfunction "22_22") (pintype "passive"))
      (node (ref "J12") (pin "25") (pinfunction "25_25") (pintype "passive"))
      (node (ref "J12") (pin "26") (pinfunction "26_26") (pintype "passive"))
      (node (ref "J12") (pin "5") (pinfunction "5_5") (pintype "passive"))
      (node (ref "J12") (pin "6") (pinfunction "6_6") (pintype "passive"))
      (node (ref "J12") (pin "9") (pinfunction "9_9") (pintype "passive"))
      (node (ref "J14") (pin "10") (pinfunction "10_10") (pintype "passive"))
      (node (ref "J14") (pin "21") (pinfunction "21_21") (pintype "passive"))
      (node (ref "J14") (pin "22") (pinfunction "22_22") (pintype "passive"))
      (node (ref "J14") (pin "25") (pinfunction "25_25") (pintype "passive"))
      (node (ref "J14") (pin "26") (pinfunction "26_26") (pintype "passive"))
      (node (ref "J14") (pin "5") (pinfunction "5_5") (pintype "passive"))
      (node (ref "J14") (pin "6") (pinfunction "6_6") (pintype "passive"))
      (node (ref "J14") (pin "9") (pinfunction "9_9") (pintype "passive"))
      (node (ref "J6") (pin "03") (pinfunction "03_03") (pintype "passive"))
      (node (ref "J6") (pin "04") (pinfunction "04_04") (pintype "passive"))
      (node (ref "R11") (pin "2") (pinfunction "2_2") (pintype "passive"))
      (node (ref "R13") (pin "2") (pinfunction "2_2") (pintype "passive"))
      (node (ref "R14") (pin "2") (pinfunction "2_2") (pintype "passive"))
      (node (ref "R16") (pin "2") (pinfunction "2_2") (pintype "passive"))
      (node (ref "R161") (pin "2") (pinfunction "2_2") (pintype "passive"))
      (node (ref "R162") (pin "2") (pinfunction "2_2") (pintype "passive"))
      (node (ref "R163") (pin "2") (pinfunction "2_2") (pintype "passive"))
      (node (ref "R25") (pin "2") (pinfunction "2_2") (pintype "passive"))
      (node (ref "R72") (pin "2") (pinfunction "2_2") (pintype "passive"))
      (node (ref "R76") (pin "2") (pinfunction "2_2") (pintype "passive"))
      (node (ref "R78") (pin "2") (pinfunction "2_2") (pintype "passive"))
      (node (ref "R9") (pin "2") (pinfunction "2_2") (pintype "passive"))
      (node (ref "U1") (pin "29") (pinfunction "EP_29") (pintype "passive"))
      (node (ref "U1") (pin "6") (pinfunction "VSS_6") (pintype "passive"))
      (node (ref "U2") (pin "29") (pinfunction "EP_29") (pintype "passive"))
      (node (ref "U2") (pin "6") (pinfunction "VSS_6") (pintype "passive"))
      (node (ref "U27") (pin "29") (pinfunction "EP_29") (pintype "passive"))
      (node (ref "U27") (pin "6") (pinfunction "VSS_6") (pintype "passive"))
      (node (ref "U55") (pin "29") (pinfunction "EP_29") (pintype "passive"))
      (node (ref "U55") (pin "6") (pinfunction "VSS_6") (pintype "passive"))
      (node (ref "U69") (pin "7") (pinfunction "GND_7") (pintype "passive"))
    )
    (net (code "76") (name "Net-(U1-A0)") (class "Default")
      (node (ref "R14") (pin "1") (pinfunction "1_1") (pintype "passive"))
      (node (ref "R15") (pin "2") (pinfunction "2_2") (pintype "passive"))
      (node (ref "U1") (pin "11") (pinfunction "A0_11") (pintype "passive"))
    )
    (net (code "77") (name "Net-(U1-A1)") (class "Default")
      (node (ref "R16") (pin "1") (pinfunction "1_1") (pintype "passive"))
      (node (ref "R24") (pin "2") (pinfunction "2_2") (pintype "passive"))
      (node (ref "U1") (pin "12") (pinfunction "A1_12") (pintype "passive"))
    )
    (net (code "78") (name "Net-(U1-A2)") (class "Default")
      (node (ref "R25") (pin "1") (pinfunction "1_1") (pintype "passive"))
      (node (ref "R26") (pin "2") (pinfunction "2_2") (pintype "passive"))
      (node (ref "U1") (pin "13") (pinfunction "A2_13") (pintype "passive"))
    )
    (net (code "79") (name "Net-(U2-A0)") (class "Default")
      (node (ref "R12") (pin "2") (pinfunction "2_2") (pintype "passive"))
      (node (ref "R13") (pin "1") (pinfunction "1_1") (pintype "passive"))
      (node (ref "U2") (pin "11") (pinfunction "A0_11") (pintype "passive"))
    )
    (net (code "80") (name "Net-(U2-A1)") (class "Default")
      (node (ref "R10") (pin "2") (pinfunction "2_2") (pintype "passive"))
      (node (ref "R11") (pin "1") (pinfunction "1_1") (pintype "passive"))
      (node (ref "U2") (pin "12") (pinfunction "A1_12") (pintype "passive"))
    )
    (net (code "81") (name "Net-(U2-A2)") (class "Default")
      (node (ref "R8") (pin "2") (pinfunction "2_2") (pintype "passive"))
      (node (ref "R9") (pin "1") (pinfunction "1_1") (pintype "passive"))
      (node (ref "U2") (pin "13") (pinfunction "A2_13") (pintype "passive"))
    )
    (net (code "82") (name "Net-(U27-A0)") (class "Default")
      (node (ref "R78") (pin "1") (pinfunction "1_1") (pintype "passive"))
      (node (ref "R79") (pin "2") (pinfunction "2_2") (pintype "passive"))
      (node (ref "U27") (pin "11") (pinfunction "A0_11") (pintype "passive"))
    )
    (net (code "83") (name "Net-(U27-A1)") (class "Default")
      (node (ref "R76") (pin "1") (pinfunction "1_1") (pintype "passive"))
      (node (ref "R77") (pin "2") (pinfunction "2_2") (pintype "passive"))
      (node (ref "U27") (pin "12") (pinfunction "A1_12") (pintype "passive"))
    )
    (net (code "84") (name "Net-(U27-A2)") (class "Default")
      (node (ref "R72") (pin "1") (pinfunction "1_1") (pintype "passive"))
      (node (ref "R73") (pin "2") (pinfunction "2_2") (pintype "passive"))
      (node (ref "U27") (pin "13") (pinfunction "A2_13") (pintype "passive"))
    )
    (net (code "85") (name "Net-(U55-A0)") (class "Default")
      (node (ref "R163") (pin "1") (pinfunction "1_1") (pintype "passive"))
      (node (ref "R176") (pin "2") (pinfunction "2_2") (pintype "passive"))
      (node (ref "U55") (pin "11") (pinfunction "A0_11") (pintype "passive"))
    )
    (net (code "86") (name "Net-(U55-A1)") (class "Default")
      (node (ref "R162") (pin "1") (pinfunction "1_1") (pintype "passive"))
      (node (ref "R175") (pin "2") (pinfunction "2_2") (pintype "passive"))
      (node (ref "U55") (pin "12") (pinfunction "A1_12") (pintype "passive"))
    )
    (net (code "87") (name "Net-(U55-A2)") (class "Default")
      (node (ref "R161") (pin "1") (pinfunction "1_1") (pintype "passive"))
      (node (ref "R174") (pin "2") (pinfunction "2_2") (pintype "passive"))
      (node (ref "U55") (pin "13") (pinfunction "A2_13") (pintype "passive"))
    )
    (net (code "88") (name "Net-(U55-GPB2)") (class "Default")
      (node (ref "R177") (pin "2") (pinfunction "2_2") (pintype "passive"))
      (node (ref "U55") (pin "27") (pinfunction "GPB2_27") (pintype "passive"))
    )
    (net (code "89") (name "Net-(U55-GPB3)") (class "Default")
      (node (ref "R180") (pin "2") (pinfunction "2_2") (pintype "passive"))
      (node (ref "U55") (pin "28") (pinfunction "GPB3_28") (pintype "passive"))
    )
    (net (code "90") (name "VCC") (class "Default")
      (node (ref "C1") (pin "1") (pinfunction "1_1") (pintype "passive"))
      (node (ref "C174") (pin "1") (pinfunction "1_1") (pintype "passive"))
      (node (ref "C2") (pin "1") (pinfunction "1_1") (pintype "passive"))
      (node (ref "C215") (pin "1") (pinfunction "1_1") (pintype "passive"))
      (node (ref "C6") (pin "1") (pinfunction "1_1") (pintype "passive"))
      (node (ref "R10") (pin "1") (pinfunction "1_1") (pintype "passive"))
      (node (ref "R12") (pin "1") (pinfunction "1_1") (pintype "passive"))
      (node (ref "R15") (pin "1") (pinfunction "1_1") (pintype "passive"))
      (node (ref "R160") (pin "1") (pinfunction "1_1") (pintype "passive"))
      (node (ref "R165") (pin "1") (pinfunction "1_1") (pintype "passive"))
      (node (ref "R166") (pin "1") (pinfunction "1_1") (pintype "passive"))
      (node (ref "R169") (pin "1") (pinfunction "1_1") (pintype "passive"))
      (node (ref "R173") (pin "1") (pinfunction "1_1") (pintype "passive"))
      (node (ref "R174") (pin "1") (pinfunction "1_1") (pintype "passive"))
      (node (ref "R175") (pin "1") (pinfunction "1_1") (pintype "passive"))
      (node (ref "R176") (pin "1") (pinfunction "1_1") (pintype "passive"))
      (node (ref "R177") (pin "1") (pinfunction "1_1") (pintype "passive"))
      (node (ref "R180") (pin "1") (pinfunction "1_1") (pintype "passive"))
      (node (ref "R24") (pin "1") (pinfunction "1_1") (pintype "passive"))
      (node (ref "R26") (pin "1") (pinfunction "1_1") (pintype "passive"))
      (node (ref "R32") (pin "1") (pinfunction "1_1") (pintype "passive"))
      (node (ref "R73") (pin "1") (pinfunction "1_1") (pintype "passive"))
      (node (ref "R77") (pin "1") (pinfunction "1_1") (pintype "passive"))
      (node (ref "R79") (pin "1") (pinfunction "1_1") (pintype "passive"))
      (node (ref "R8") (pin "1") (pinfunction "1_1") (pintype "passive"))
      (node (ref "U1") (pin "5") (pinfunction "VDD_5") (pintype "passive"))
      (node (ref "U2") (pin "5") (pinfunction "VDD_5") (pintype "passive"))
      (node (ref "U27") (pin "5") (pinfunction "VDD_5") (pintype "passive"))
      (node (ref "U55") (pin "5") (pinfunction "VDD_5") (pintype "passive"))
      (node (ref "U69") (pin "14") (pinfunction "VCC_14") (pintype "power_in"))
    )
    (net (code "91") (name "unconnected-(J6-Pad09)") (class "Default")
      (node (ref "J6") (pin "09") (pinfunction "09_09") (pintype "passive"))
    )
    (net (code "92") (name "unconnected-(J6-Pad10)") (class "Default")
      (node (ref "J6") (pin "10") (pinfunction "10_10") (pintype "passive"))
    )
    (net (code "93") (name "unconnected-(J12-Pad3)") (class "Default")
      (node (ref "J12") (pin "3") (pinfunction "3_3") (pintype "passive"))
    )
    (net (code "94") (name "unconnected-(J12-Pad4)") (class "Default")
      (node (ref "J12") (pin "4") (pinfunction "4_4") (pintype "passive"))
    )
    (net (code "95") (name "unconnected-(J12-Pad11)") (class "Default")
      (node (ref "J12") (pin "11") (pinfunction "11_11") (pintype "passive"))
    )
    (net (code "96") (name "unconnected-(J12-Pad23)") (class "Default")
      (node (ref "J12") (pin "23") (pinfunction "23_23") (pintype "passive"))
    )
    (net (code "97") (name "unconnected-(J12-Pad24)") (class "Default")
      (node (ref "J12") (pin "24") (pinfunction "24_24") (pintype "passive"))
    )
    (net (code "98") (name "unconnected-(J12-Pad27)") (class "Default")
      (node (ref "J12") (pin "27") (pinfunction "27_27") (pintype "passive"))
    )
    (net (code "99") (name "unconnected-(J12-Pad28)") (class "Default")
      (node (ref "J12") (pin "28") (pinfunction "28_28") (pintype "passive"))
    )
    (net (code "100") (name "unconnected-(J14-Pad3)") (class "Default")
      (node (ref "J14") (pin "3") (pinfunction "3_3") (pintype "passive"))
    )
    (net (code "101") (name "unconnected-(J14-Pad4)") (class "Default")
      (node (ref "J14") (pin "4") (pinfunction "4_4") (pintype "passive"))
    )
    (net (code "102") (name "unconnected-(J14-Pad11)") (class "Default")
      (node (ref "J14") (pin "11") (pinfunction "11_11") (pintype "passive"))
    )
    (net (code "103") (name "unconnected-(J14-Pad23)") (class "Default")
      (node (ref "J14") (pin "23") (pinfunction "23_23") (pintype "passive"))
    )
    (net (code "104") (name "unconnected-(J14-Pad24)") (class "Default")
      (node (ref "J14") (pin "24") (pinfunction "24_24") (pintype "passive"))
    )
    (net (code "105") (name "unconnected-(J14-Pad27)") (class "Default")
      (node (ref "J14") (pin "27") (pinfunction "27_27") (pintype "passive"))
    )
    (net (code "106") (name "unconnected-(J14-Pad28)") (class "Default")
      (node (ref "J14") (pin "28") (pinfunction "28_28") (pintype "passive"))
    )
    (net (code "107") (name "unconnected-(U2-GPB1-Pad26)") (class "Default")
      (node (ref "U2") (pin "26") (pinfunction "GPB1_26") (pintype "passive+no_connect"))
    )
    (net (code "108") (name "unconnected-(U2-GPB2-Pad27)") (class "Default")
      (node (ref "U2") (pin "27") (pinfunction "GPB2_27") (pintype "passive+no_connect"))
    )
    (net (code "109") (name "unconnected-(U2-GPB3-Pad28)") (class "Default")
      (node (ref "U2") (pin "28") (pinfunction "GPB3_28") (pintype "passive+no_connect"))
    )
    (net (code "110") (name "unconnected-(U2-GPB4-Pad1)") (class "Default")
      (node (ref "U2") (pin "1") (pinfunction "GPB4_1") (pintype "passive+no_connect"))
    )
    (net (code "111") (name "unconnected-(U2-GPB5-Pad2)") (class "Default")
      (node (ref "U2") (pin "2") (pinfunction "GPB5_2") (pintype "passive+no_connect"))
    )
    (net (code "112") (name "unconnected-(U2-GPB6-Pad3)") (class "Default")
      (node (ref "U2") (pin "3") (pinfunction "GPB6_3") (pintype "passive+no_connect"))
    )
    (net (code "113") (name "unconnected-(U27-GPA0-Pad17)") (class "Default")
      (node (ref "U27") (pin "17") (pinfunction "GPA0_17") (pintype "passive+no_connect"))
    )
    (net (code "114") (name "unconnected-(U27-GPA1-Pad18)") (class "Default")
      (node (ref "U27") (pin "18") (pinfunction "GPA1_18") (pintype "passive+no_connect"))
    )
    (net (code "115") (name "unconnected-(U27-GPB6-Pad3)") (class "Default")
      (node (ref "U27") (pin "3") (pinfunction "GPB6_3") (pintype "passive+no_connect"))
    )
    (net (code "116") (name "unconnected-(U27-GPB7-Pad4)") (class "Default")
      (node (ref "U27") (pin "4") (pinfunction "GPB7_4") (pintype "passive+no_connect"))
    )
    (net (code "117") (name "unconnected-(U55-GPA3-Pad20)") (class "Default")
      (node (ref "U55") (pin "20") (pinfunction "GPA3_20") (pintype "passive+no_connect"))
    )
    (net (code "118") (name "unconnected-(U55-GPA4-Pad21)") (class "Default")
      (node (ref "U55") (pin "21") (pinfunction "GPA4_21") (pintype "passive+no_connect"))
    )
    (net (code "119") (name "unconnected-(U55-GPA5-Pad22)") (class "Default")
      (node (ref "U55") (pin "22") (pinfunction "GPA5_22") (pintype "passive+no_connect"))
    )
  )
)
